# TripWire.net
KiCad netlist of a schematic drawn in EAGLE
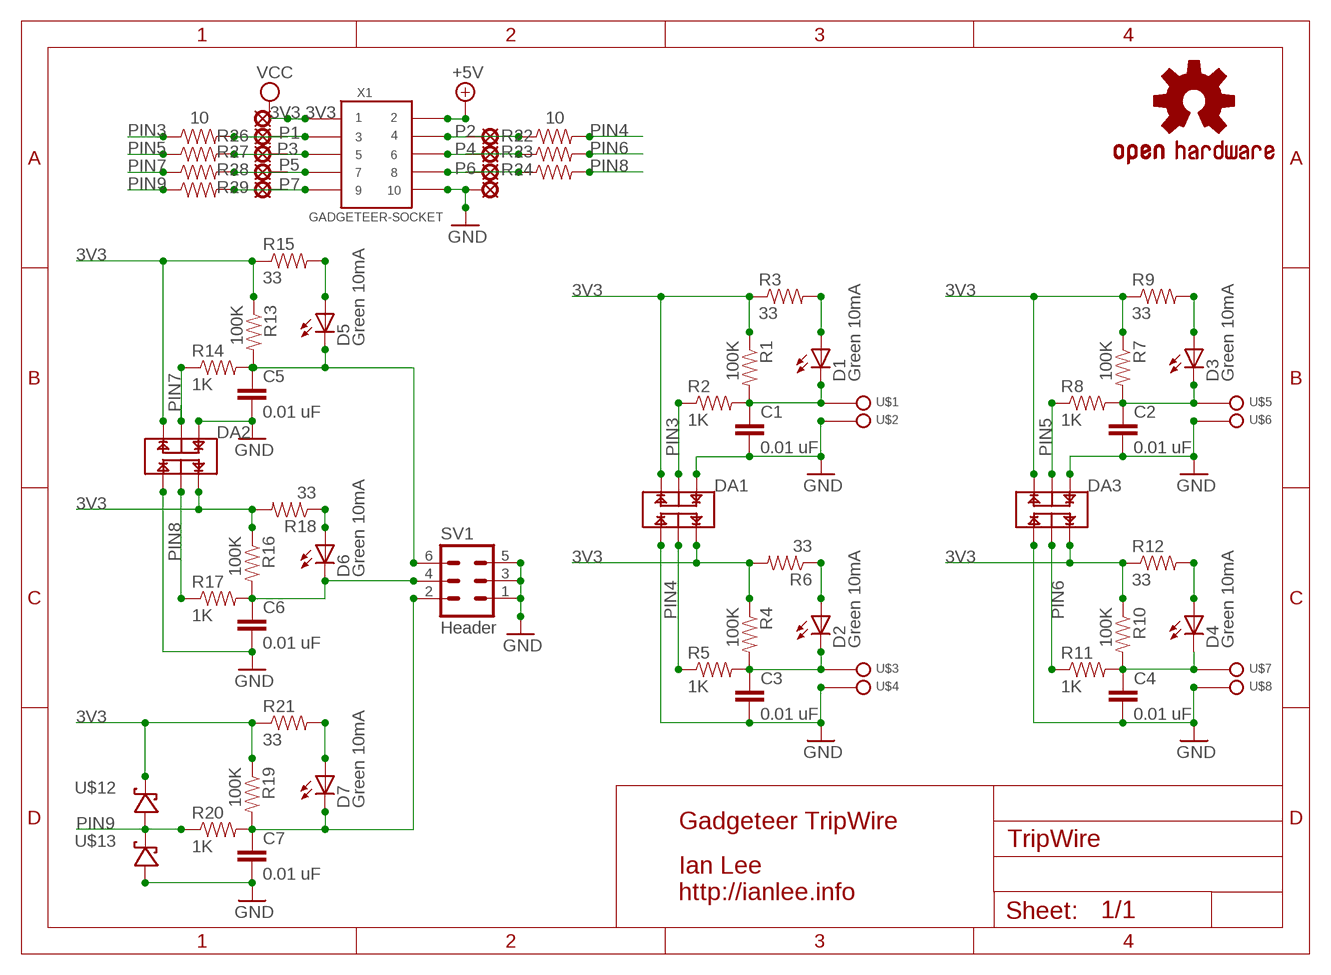
[diagram p0: schematic, sheet 1]

(export (version "E")
  (design (tool "Eeschema 10.0.6"))
  (components
    (comp (ref "3V3")
      (value "LSP11")
      (footprint "eagle-import:LSP11")
      (libsource (lib "eagle-import") (part "LSP11"))
    )
    (comp (ref "C1")
      (value "0.01 uF")
      (footprint "eagle-import:0603-CAP")
      (libsource (lib "eagle-import") (part "CAP0603-CAP"))
    )
    (comp (ref "C2")
      (value "0.01 uF")
      (footprint "eagle-import:0603-CAP")
      (libsource (lib "eagle-import") (part "CAP0603-CAP"))
    )
    (comp (ref "C3")
      (value "0.01 uF")
      (footprint "eagle-import:0603-CAP")
      (libsource (lib "eagle-import") (part "CAP0603-CAP"))
    )
    (comp (ref "C4")
      (value "0.01 uF")
      (footprint "eagle-import:0603-CAP")
      (libsource (lib "eagle-import") (part "CAP0603-CAP"))
    )
    (comp (ref "C5")
      (value "0.01 uF")
      (footprint "eagle-import:0603-CAP")
      (libsource (lib "eagle-import") (part "CAP0603-CAP"))
    )
    (comp (ref "C6")
      (value "0.01 uF")
      (footprint "eagle-import:0603-CAP")
      (libsource (lib "eagle-import") (part "CAP0603-CAP"))
    )
    (comp (ref "C7")
      (value "0.01 uF")
      (footprint "eagle-import:0603-CAP")
      (libsource (lib "eagle-import") (part "CAP0603-CAP"))
    )
    (comp (ref "D1")
      (value "Green 10mA")
      (footprint "eagle-import:LED-0603")
      (libsource (lib "eagle-import") (part "LED-YELLOW0603"))
    )
    (comp (ref "D2")
      (value "Green 10mA")
      (footprint "eagle-import:LED-0603")
      (libsource (lib "eagle-import") (part "LED-YELLOW0603"))
    )
    (comp (ref "D3")
      (value "Green 10mA")
      (footprint "eagle-import:LED-0603")
      (libsource (lib "eagle-import") (part "LED-YELLOW0603"))
    )
    (comp (ref "D4")
      (value "Green 10mA")
      (footprint "eagle-import:LED-0603")
      (libsource (lib "eagle-import") (part "LED-YELLOW0603"))
    )
    (comp (ref "D5")
      (value "Green 10mA")
      (footprint "eagle-import:LED-0603")
      (libsource (lib "eagle-import") (part "LED-YELLOW0603"))
    )
    (comp (ref "D6")
      (value "Green 10mA")
      (footprint "eagle-import:LED-0603")
      (libsource (lib "eagle-import") (part "LED-YELLOW0603"))
    )
    (comp (ref "D7")
      (value "Green 10mA")
      (footprint "eagle-import:LED-0603")
      (libsource (lib "eagle-import") (part "LED-YELLOW0603"))
    )
    (comp (ref "DA1")
      (value "BAT54SDW")
      (footprint "eagle-import:SOT-363")
      (libsource (lib "eagle-import") (part "BAT54SDW"))
    )
    (comp (ref "DA2")
      (value "BAT54SDW")
      (footprint "eagle-import:SOT-363")
      (libsource (lib "eagle-import") (part "BAT54SDW"))
    )
    (comp (ref "DA3")
      (value "BAT54SDW")
      (footprint "eagle-import:SOT-363")
      (libsource (lib "eagle-import") (part "BAT54SDW"))
    )
    (comp (ref "GND")
      (value "LSP11")
      (footprint "eagle-import:LSP11")
      (libsource (lib "eagle-import") (part "LSP11"))
    )
    (comp (ref "LOGO1")
      (value "OSHW-LOGOM")
      (footprint "eagle-import:OSHW-LOGO-M")
      (libsource (lib "eagle-import") (part "OSHW-LOGOM"))
    )
    (comp (ref "P1")
      (value "LSP11")
      (footprint "eagle-import:LSP11")
      (libsource (lib "eagle-import") (part "LSP11"))
    )
    (comp (ref "P2")
      (value "LSP11")
      (footprint "eagle-import:LSP11")
      (libsource (lib "eagle-import") (part "LSP11"))
    )
    (comp (ref "P3")
      (value "LSP11")
      (footprint "eagle-import:LSP11")
      (libsource (lib "eagle-import") (part "LSP11"))
    )
    (comp (ref "P4")
      (value "LSP11")
      (footprint "eagle-import:LSP11")
      (libsource (lib "eagle-import") (part "LSP11"))
    )
    (comp (ref "P5")
      (value "LSP11")
      (footprint "eagle-import:LSP11")
      (libsource (lib "eagle-import") (part "LSP11"))
    )
    (comp (ref "P6")
      (value "LSP11")
      (footprint "eagle-import:LSP11")
      (libsource (lib "eagle-import") (part "LSP11"))
    )
    (comp (ref "P7")
      (value "LSP11")
      (footprint "eagle-import:LSP11")
      (libsource (lib "eagle-import") (part "LSP11"))
    )
    (comp (ref "R1")
      (value "100K")
      (footprint "eagle-import:0603-RES")
      (libsource (lib "eagle-import") (part "RESISTOR0603-RES"))
    )
    (comp (ref "R2")
      (value "1K")
      (footprint "eagle-import:0603-RES")
      (libsource (lib "eagle-import") (part "RESISTOR0603-RES"))
    )
    (comp (ref "R3")
      (value "33")
      (footprint "eagle-import:0603-RES")
      (libsource (lib "eagle-import") (part "RESISTOR0603-RES"))
    )
    (comp (ref "R4")
      (value "100K")
      (footprint "eagle-import:0603-RES")
      (libsource (lib "eagle-import") (part "RESISTOR0603-RES"))
    )
    (comp (ref "R5")
      (value "1K")
      (footprint "eagle-import:0603-RES")
      (libsource (lib "eagle-import") (part "RESISTOR0603-RES"))
    )
    (comp (ref "R6")
      (value "33")
      (footprint "eagle-import:0603-RES")
      (libsource (lib "eagle-import") (part "RESISTOR0603-RES"))
    )
    (comp (ref "R7")
      (value "100K")
      (footprint "eagle-import:0603-RES")
      (libsource (lib "eagle-import") (part "RESISTOR0603-RES"))
    )
    (comp (ref "R8")
      (value "1K")
      (footprint "eagle-import:0603-RES")
      (libsource (lib "eagle-import") (part "RESISTOR0603-RES"))
    )
    (comp (ref "R9")
      (value "33")
      (footprint "eagle-import:0603-RES")
      (libsource (lib "eagle-import") (part "RESISTOR0603-RES"))
    )
    (comp (ref "R10")
      (value "100K")
      (footprint "eagle-import:0603-RES")
      (libsource (lib "eagle-import") (part "RESISTOR0603-RES"))
    )
    (comp (ref "R11")
      (value "1K")
      (footprint "eagle-import:0603-RES")
      (libsource (lib "eagle-import") (part "RESISTOR0603-RES"))
    )
    (comp (ref "R12")
      (value "33")
      (footprint "eagle-import:0603-RES")
      (libsource (lib "eagle-import") (part "RESISTOR0603-RES"))
    )
    (comp (ref "R13")
      (value "100K")
      (footprint "eagle-import:0603-RES")
      (libsource (lib "eagle-import") (part "RESISTOR0603-RES"))
    )
    (comp (ref "R14")
      (value "1K")
      (footprint "eagle-import:0603-RES")
      (libsource (lib "eagle-import") (part "RESISTOR0603-RES"))
    )
    (comp (ref "R15")
      (value "33")
      (footprint "eagle-import:0603-RES")
      (libsource (lib "eagle-import") (part "RESISTOR0603-RES"))
    )
    (comp (ref "R16")
      (value "100K")
      (footprint "eagle-import:0603-RES")
      (libsource (lib "eagle-import") (part "RESISTOR0603-RES"))
    )
    (comp (ref "R17")
      (value "1K")
      (footprint "eagle-import:0603-RES")
      (libsource (lib "eagle-import") (part "RESISTOR0603-RES"))
    )
    (comp (ref "R18")
      (value "33")
      (footprint "eagle-import:0603-RES")
      (libsource (lib "eagle-import") (part "RESISTOR0603-RES"))
    )
    (comp (ref "R19")
      (value "100K")
      (footprint "eagle-import:0603-RES")
      (libsource (lib "eagle-import") (part "RESISTOR0603-RES"))
    )
    (comp (ref "R20")
      (value "1K")
      (footprint "eagle-import:0603-RES")
      (libsource (lib "eagle-import") (part "RESISTOR0603-RES"))
    )
    (comp (ref "R21")
      (value "33")
      (footprint "eagle-import:0603-RES")
      (libsource (lib "eagle-import") (part "RESISTOR0603-RES"))
    )
    (comp (ref "R22")
      (value "10")
      (footprint "eagle-import:0603-RES")
      (libsource (lib "eagle-import") (part "RESISTOR0603-RES"))
    )
    (comp (ref "R23")
      (value "10")
      (footprint "eagle-import:0603-RES")
      (libsource (lib "eagle-import") (part "RESISTOR0603-RES"))
    )
    (comp (ref "R24")
      (value "10")
      (footprint "eagle-import:0603-RES")
      (libsource (lib "eagle-import") (part "RESISTOR0603-RES"))
    )
    (comp (ref "R26")
      (value "10")
      (footprint "eagle-import:0603-RES")
      (libsource (lib "eagle-import") (part "RESISTOR0603-RES"))
    )
    (comp (ref "R27")
      (value "10")
      (footprint "eagle-import:0603-RES")
      (libsource (lib "eagle-import") (part "RESISTOR0603-RES"))
    )
    (comp (ref "R28")
      (value "10")
      (footprint "eagle-import:0603-RES")
      (libsource (lib "eagle-import") (part "RESISTOR0603-RES"))
    )
    (comp (ref "R29")
      (value "10")
      (footprint "eagle-import:0603-RES")
      (libsource (lib "eagle-import") (part "RESISTOR0603-RES"))
    )
    (comp (ref "SV1")
      (value "Header")
      (footprint "eagle-import:MA03-2")
      (libsource (lib "eagle-import") (part "MA03-2"))
    )
    (comp (ref "U$1")
      (value "SPADE-TERMINALPTH")
      (footprint "eagle-import:SPADE-TERMINAL")
      (libsource (lib "eagle-import") (part "SPADE-TERMINALPTH"))
    )
    (comp (ref "U$2")
      (value "SPADE-TERMINALPTH")
      (footprint "eagle-import:SPADE-TERMINAL")
      (libsource (lib "eagle-import") (part "SPADE-TERMINALPTH"))
    )
    (comp (ref "U$3")
      (value "SPADE-TERMINALPTH")
      (footprint "eagle-import:SPADE-TERMINAL")
      (libsource (lib "eagle-import") (part "SPADE-TERMINALPTH"))
    )
    (comp (ref "U$4")
      (value "SPADE-TERMINALPTH")
      (footprint "eagle-import:SPADE-TERMINAL")
      (libsource (lib "eagle-import") (part "SPADE-TERMINALPTH"))
    )
    (comp (ref "U$5")
      (value "SPADE-TERMINALPTH")
      (footprint "eagle-import:SPADE-TERMINAL")
      (libsource (lib "eagle-import") (part "SPADE-TERMINALPTH"))
    )
    (comp (ref "U$6")
      (value "SPADE-TERMINALPTH")
      (footprint "eagle-import:SPADE-TERMINAL")
      (libsource (lib "eagle-import") (part "SPADE-TERMINALPTH"))
    )
    (comp (ref "U$7")
      (value "SPADE-TERMINALPTH")
      (footprint "eagle-import:SPADE-TERMINAL")
      (libsource (lib "eagle-import") (part "SPADE-TERMINALPTH"))
    )
    (comp (ref "U$8")
      (value "SPADE-TERMINALPTH")
      (footprint "eagle-import:SPADE-TERMINAL")
      (libsource (lib "eagle-import") (part "SPADE-TERMINALPTH"))
    )
    (comp (ref "U$12")
      (value "BAT42-SCHOTTKY-DIODE")
      (footprint "eagle-import:SOD-523F")
      (libsource (lib "eagle-import") (part "BAT42-SCHOTTKY-DIODE"))
    )
    (comp (ref "U$13")
      (value "BAT42-SCHOTTKY-DIODE")
      (footprint "eagle-import:SOD-523F")
      (libsource (lib "eagle-import") (part "BAT42-SCHOTTKY-DIODE"))
    )
    (comp (ref "X1")
      (value "GADGETEER-SOCKET")
      (footprint "eagle-import:2X5_1.27MM")
      (libsource (lib "eagle-import") (part "GADGETEER-SOCKET"))
    )
  )
  (nets
    (net (code "1") (name "+5V") (class "Default")
      (node (ref "X1") (pin "2") (pinfunction "P$2_2") (pintype "bidirectional"))
    )
    (net (code "2") (name "/PIN3") (class "Default")
      (node (ref "DA1") (pin "P$5") (pinfunction "AC2_P$5") (pintype "bidirectional"))
      (node (ref "R2") (pin "1") (pinfunction "1_1") (pintype "passive"))
      (node (ref "R26") (pin "1") (pinfunction "1_1") (pintype "passive"))
    )
    (net (code "3") (name "/PIN4") (class "Default")
      (node (ref "DA1") (pin "P$0") (pinfunction "AC1_P$0") (pintype "bidirectional"))
      (node (ref "R22") (pin "2") (pinfunction "2_2") (pintype "passive"))
      (node (ref "R5") (pin "1") (pinfunction "1_1") (pintype "passive"))
    )
    (net (code "4") (name "/PIN5") (class "Default")
      (node (ref "DA3") (pin "P$5") (pinfunction "AC2_P$5") (pintype "bidirectional"))
      (node (ref "R27") (pin "1") (pinfunction "1_1") (pintype "passive"))
      (node (ref "R8") (pin "1") (pinfunction "1_1") (pintype "passive"))
    )
    (net (code "5") (name "/PIN6") (class "Default")
      (node (ref "DA3") (pin "P$0") (pinfunction "AC1_P$0") (pintype "bidirectional"))
      (node (ref "R11") (pin "1") (pinfunction "1_1") (pintype "passive"))
      (node (ref "R23") (pin "2") (pinfunction "2_2") (pintype "passive"))
    )
    (net (code "6") (name "/PIN7") (class "Default")
      (node (ref "DA2") (pin "P$5") (pinfunction "AC2_P$5") (pintype "bidirectional"))
      (node (ref "R14") (pin "1") (pinfunction "1_1") (pintype "passive"))
      (node (ref "R28") (pin "1") (pinfunction "1_1") (pintype "passive"))
    )
    (net (code "7") (name "/PIN8") (class "Default")
      (node (ref "DA2") (pin "P$0") (pinfunction "AC1_P$0") (pintype "bidirectional"))
      (node (ref "R17") (pin "1") (pinfunction "1_1") (pintype "passive"))
      (node (ref "R24") (pin "2") (pinfunction "2_2") (pintype "passive"))
    )
    (net (code "8") (name "/PIN9") (class "Default")
      (node (ref "R20") (pin "1") (pinfunction "1_1") (pintype "passive"))
      (node (ref "R29") (pin "1") (pinfunction "1_1") (pintype "passive"))
      (node (ref "U$12") (pin "P$2") (pinfunction "P$2_P$2") (pintype "bidirectional"))
      (node (ref "U$13") (pin "P$1") (pinfunction "P$1_P$1") (pintype "bidirectional"))
    )
    (net (code "9") (name "GND") (class "Default")
      (node (ref "C1") (pin "2") (pinfunction "2_2") (pintype "passive"))
      (node (ref "C2") (pin "2") (pinfunction "2_2") (pintype "passive"))
      (node (ref "C3") (pin "2") (pinfunction "2_2") (pintype "passive"))
      (node (ref "C4") (pin "2") (pinfunction "2_2") (pintype "passive"))
      (node (ref "C5") (pin "2") (pinfunction "2_2") (pintype "passive"))
      (node (ref "C6") (pin "2") (pinfunction "2_2") (pintype "passive"))
      (node (ref "C7") (pin "2") (pinfunction "2_2") (pintype "passive"))
      (node (ref "DA1") (pin "P$2") (pinfunction "A2_P$2") (pintype "bidirectional"))
      (node (ref "DA1") (pin "P$3") (pinfunction "A1_P$3") (pintype "bidirectional"))
      (node (ref "DA2") (pin "P$2") (pinfunction "A2_P$2") (pintype "bidirectional"))
      (node (ref "DA2") (pin "P$3") (pinfunction "A1_P$3") (pintype "bidirectional"))
      (node (ref "DA3") (pin "P$2") (pinfunction "A2_P$2") (pintype "bidirectional"))
      (node (ref "DA3") (pin "P$3") (pinfunction "A1_P$3") (pintype "bidirectional"))
      (node (ref "GND") (pin "MP") (pinfunction "MP_MP") (pintype "passive"))
      (node (ref "SV1") (pin "1") (pinfunction "1_1") (pintype "passive"))
      (node (ref "SV1") (pin "3") (pinfunction "3_3") (pintype "passive"))
      (node (ref "SV1") (pin "5") (pinfunction "5_5") (pintype "passive"))
      (node (ref "U$13") (pin "P$2") (pinfunction "P$2_P$2") (pintype "bidirectional"))
      (node (ref "U$2") (pin "P$1") (pinfunction "P$1_P$1") (pintype "bidirectional"))
      (node (ref "U$4") (pin "P$1") (pinfunction "P$1_P$1") (pintype "bidirectional"))
      (node (ref "U$6") (pin "P$1") (pinfunction "P$1_P$1") (pintype "bidirectional"))
      (node (ref "U$8") (pin "P$1") (pinfunction "P$1_P$1") (pintype "bidirectional"))
      (node (ref "X1") (pin "10") (pinfunction "P$10_10") (pintype "bidirectional"))
    )
    (net (code "10") (name "Net-(C1-Pad1)") (class "Default")
      (node (ref "C1") (pin "1") (pinfunction "1_1") (pintype "passive"))
      (node (ref "D1") (pin "C") (pinfunction "C_C") (pintype "passive"))
      (node (ref "R1") (pin "2") (pinfunction "2_2") (pintype "passive"))
      (node (ref "R2") (pin "2") (pinfunction "2_2") (pintype "passive"))
      (node (ref "U$1") (pin "P$1") (pinfunction "P$1_P$1") (pintype "bidirectional"))
    )
    (net (code "11") (name "Net-(C2-Pad1)") (class "Default")
      (node (ref "C2") (pin "1") (pinfunction "1_1") (pintype "passive"))
      (node (ref "D3") (pin "C") (pinfunction "C_C") (pintype "passive"))
      (node (ref "R7") (pin "2") (pinfunction "2_2") (pintype "passive"))
      (node (ref "R8") (pin "2") (pinfunction "2_2") (pintype "passive"))
      (node (ref "U$5") (pin "P$1") (pinfunction "P$1_P$1") (pintype "bidirectional"))
    )
    (net (code "12") (name "Net-(C3-Pad1)") (class "Default")
      (node (ref "C3") (pin "1") (pinfunction "1_1") (pintype "passive"))
      (node (ref "D2") (pin "C") (pinfunction "C_C") (pintype "passive"))
      (node (ref "R4") (pin "2") (pinfunction "2_2") (pintype "passive"))
      (node (ref "R5") (pin "2") (pinfunction "2_2") (pintype "passive"))
      (node (ref "U$3") (pin "P$1") (pinfunction "P$1_P$1") (pintype "bidirectional"))
    )
    (net (code "13") (name "Net-(C4-Pad1)") (class "Default")
      (node (ref "C4") (pin "1") (pinfunction "1_1") (pintype "passive"))
      (node (ref "D4") (pin "C") (pinfunction "C_C") (pintype "passive"))
      (node (ref "R10") (pin "2") (pinfunction "2_2") (pintype "passive"))
      (node (ref "R11") (pin "2") (pinfunction "2_2") (pintype "passive"))
      (node (ref "U$7") (pin "P$1") (pinfunction "P$1_P$1") (pintype "bidirectional"))
    )
    (net (code "14") (name "Net-(C5-Pad1)") (class "Default")
      (node (ref "C5") (pin "1") (pinfunction "1_1") (pintype "passive"))
      (node (ref "D5") (pin "C") (pinfunction "C_C") (pintype "passive"))
      (node (ref "R13") (pin "2") (pinfunction "2_2") (pintype "passive"))
      (node (ref "R14") (pin "2") (pinfunction "2_2") (pintype "passive"))
      (node (ref "SV1") (pin "6") (pinfunction "6_6") (pintype "passive"))
    )
    (net (code "15") (name "Net-(C6-Pad1)") (class "Default")
      (node (ref "C6") (pin "1") (pinfunction "1_1") (pintype "passive"))
      (node (ref "D6") (pin "C") (pinfunction "C_C") (pintype "passive"))
      (node (ref "R16") (pin "2") (pinfunction "2_2") (pintype "passive"))
      (node (ref "R17") (pin "2") (pinfunction "2_2") (pintype "passive"))
      (node (ref "SV1") (pin "4") (pinfunction "4_4") (pintype "passive"))
    )
    (net (code "16") (name "Net-(C7-Pad1)") (class "Default")
      (node (ref "C7") (pin "1") (pinfunction "1_1") (pintype "passive"))
      (node (ref "D7") (pin "C") (pinfunction "C_C") (pintype "passive"))
      (node (ref "R19") (pin "2") (pinfunction "2_2") (pintype "passive"))
      (node (ref "R20") (pin "2") (pinfunction "2_2") (pintype "passive"))
      (node (ref "SV1") (pin "2") (pinfunction "2_2") (pintype "passive"))
    )
    (net (code "17") (name "Net-(D1-PadA)") (class "Default")
      (node (ref "D1") (pin "A") (pinfunction "A_A") (pintype "passive"))
      (node (ref "R3") (pin "2") (pinfunction "2_2") (pintype "passive"))
    )
    (net (code "18") (name "Net-(D2-PadA)") (class "Default")
      (node (ref "D2") (pin "A") (pinfunction "A_A") (pintype "passive"))
      (node (ref "R6") (pin "1") (pinfunction "1_1") (pintype "passive"))
    )
    (net (code "19") (name "Net-(D3-PadA)") (class "Default")
      (node (ref "D3") (pin "A") (pinfunction "A_A") (pintype "passive"))
      (node (ref "R9") (pin "2") (pinfunction "2_2") (pintype "passive"))
    )
    (net (code "20") (name "Net-(D4-PadA)") (class "Default")
      (node (ref "D4") (pin "A") (pinfunction "A_A") (pintype "passive"))
      (node (ref "R12") (pin "2") (pinfunction "2_2") (pintype "passive"))
    )
    (net (code "21") (name "Net-(D5-PadA)") (class "Default")
      (node (ref "D5") (pin "A") (pinfunction "A_A") (pintype "passive"))
      (node (ref "R15") (pin "2") (pinfunction "2_2") (pintype "passive"))
    )
    (net (code "22") (name "Net-(D6-PadA)") (class "Default")
      (node (ref "D6") (pin "A") (pinfunction "A_A") (pintype "passive"))
      (node (ref "R18") (pin "1") (pinfunction "1_1") (pintype "passive"))
    )
    (net (code "23") (name "Net-(D7-PadA)") (class "Default")
      (node (ref "D7") (pin "A") (pinfunction "A_A") (pintype "passive"))
      (node (ref "R21") (pin "2") (pinfunction "2_2") (pintype "passive"))
    )
    (net (code "24") (name "Net-(X1-P$3)") (class "Default")
      (node (ref "P1") (pin "MP") (pinfunction "MP_MP") (pintype "passive"))
      (node (ref "R26") (pin "2") (pinfunction "2_2") (pintype "passive"))
      (node (ref "X1") (pin "3") (pinfunction "P$3_3") (pintype "bidirectional"))
    )
    (net (code "25") (name "Net-(X1-P$4)") (class "Default")
      (node (ref "P2") (pin "MP") (pinfunction "MP_MP") (pintype "passive"))
      (node (ref "R22") (pin "1") (pinfunction "1_1") (pintype "passive"))
      (node (ref "X1") (pin "4") (pinfunction "P$4_4") (pintype "bidirectional"))
    )
    (net (code "26") (name "Net-(X1-P$5)") (class "Default")
      (node (ref "P3") (pin "MP") (pinfunction "MP_MP") (pintype "passive"))
      (node (ref "R27") (pin "2") (pinfunction "2_2") (pintype "passive"))
      (node (ref "X1") (pin "5") (pinfunction "P$5_5") (pintype "bidirectional"))
    )
    (net (code "27") (name "Net-(X1-P$6)") (class "Default")
      (node (ref "P4") (pin "MP") (pinfunction "MP_MP") (pintype "passive"))
      (node (ref "R23") (pin "1") (pinfunction "1_1") (pintype "passive"))
      (node (ref "X1") (pin "6") (pinfunction "P$6_6") (pintype "bidirectional"))
    )
    (net (code "28") (name "Net-(X1-P$7)") (class "Default")
      (node (ref "P5") (pin "MP") (pinfunction "MP_MP") (pintype "passive"))
      (node (ref "R28") (pin "2") (pinfunction "2_2") (pintype "passive"))
      (node (ref "X1") (pin "7") (pinfunction "P$7_7") (pintype "bidirectional"))
    )
    (net (code "29") (name "Net-(X1-P$8)") (class "Default")
      (node (ref "P6") (pin "MP") (pinfunction "MP_MP") (pintype "passive"))
      (node (ref "R24") (pin "1") (pinfunction "1_1") (pintype "passive"))
      (node (ref "X1") (pin "8") (pinfunction "P$8_8") (pintype "bidirectional"))
    )
    (net (code "30") (name "Net-(X1-P$9)") (class "Default")
      (node (ref "P7") (pin "MP") (pinfunction "MP_MP") (pintype "passive"))
      (node (ref "R29") (pin "2") (pinfunction "2_2") (pintype "passive"))
      (node (ref "X1") (pin "9") (pinfunction "P$9_9") (pintype "bidirectional"))
    )
    (net (code "31") (name "VCC") (class "Default")
      (node (ref "3V3") (pin "MP") (pinfunction "MP_MP") (pintype "passive"))
      (node (ref "DA1") (pin "P$1") (pinfunction "C2_P$1") (pintype "bidirectional"))
      (node (ref "DA1") (pin "P$4") (pinfunction "C1_P$4") (pintype "bidirectional"))
      (node (ref "DA2") (pin "P$1") (pinfunction "C2_P$1") (pintype "bidirectional"))
      (node (ref "DA2") (pin "P$4") (pinfunction "C1_P$4") (pintype "bidirectional"))
      (node (ref "DA3") (pin "P$1") (pinfunction "C2_P$1") (pintype "bidirectional"))
      (node (ref "DA3") (pin "P$4") (pinfunction "C1_P$4") (pintype "bidirectional"))
      (node (ref "R1") (pin "1") (pinfunction "1_1") (pintype "passive"))
      (node (ref "R10") (pin "1") (pinfunction "1_1") (pintype "passive"))
      (node (ref "R12") (pin "1") (pinfunction "1_1") (pintype "passive"))
      (node (ref "R13") (pin "1") (pinfunction "1_1") (pintype "passive"))
      (node (ref "R15") (pin "1") (pinfunction "1_1") (pintype "passive"))
      (node (ref "R16") (pin "1") (pinfunction "1_1") (pintype "passive"))
      (node (ref "R18") (pin "2") (pinfunction "2_2") (pintype "passive"))
      (node (ref "R19") (pin "1") (pinfunction "1_1") (pintype "passive"))
      (node (ref "R21") (pin "1") (pinfunction "1_1") (pintype "passive"))
      (node (ref "R3") (pin "1") (pinfunction "1_1") (pintype "passive"))
      (node (ref "R4") (pin "1") (pinfunction "1_1") (pintype "passive"))
      (node (ref "R6") (pin "2") (pinfunction "2_2") (pintype "passive"))
      (node (ref "R7") (pin "1") (pinfunction "1_1") (pintype "passive"))
      (node (ref "R9") (pin "1") (pinfunction "1_1") (pintype "passive"))
      (node (ref "U$12") (pin "P$1") (pinfunction "P$1_P$1") (pintype "bidirectional"))
      (node (ref "X1") (pin "1") (pinfunction "P$1_1") (pintype "bidirectional"))
    )
  )
)
